# I2C_SWITCH.net
KiCad netlist of a schematic drawn in Altium Designer
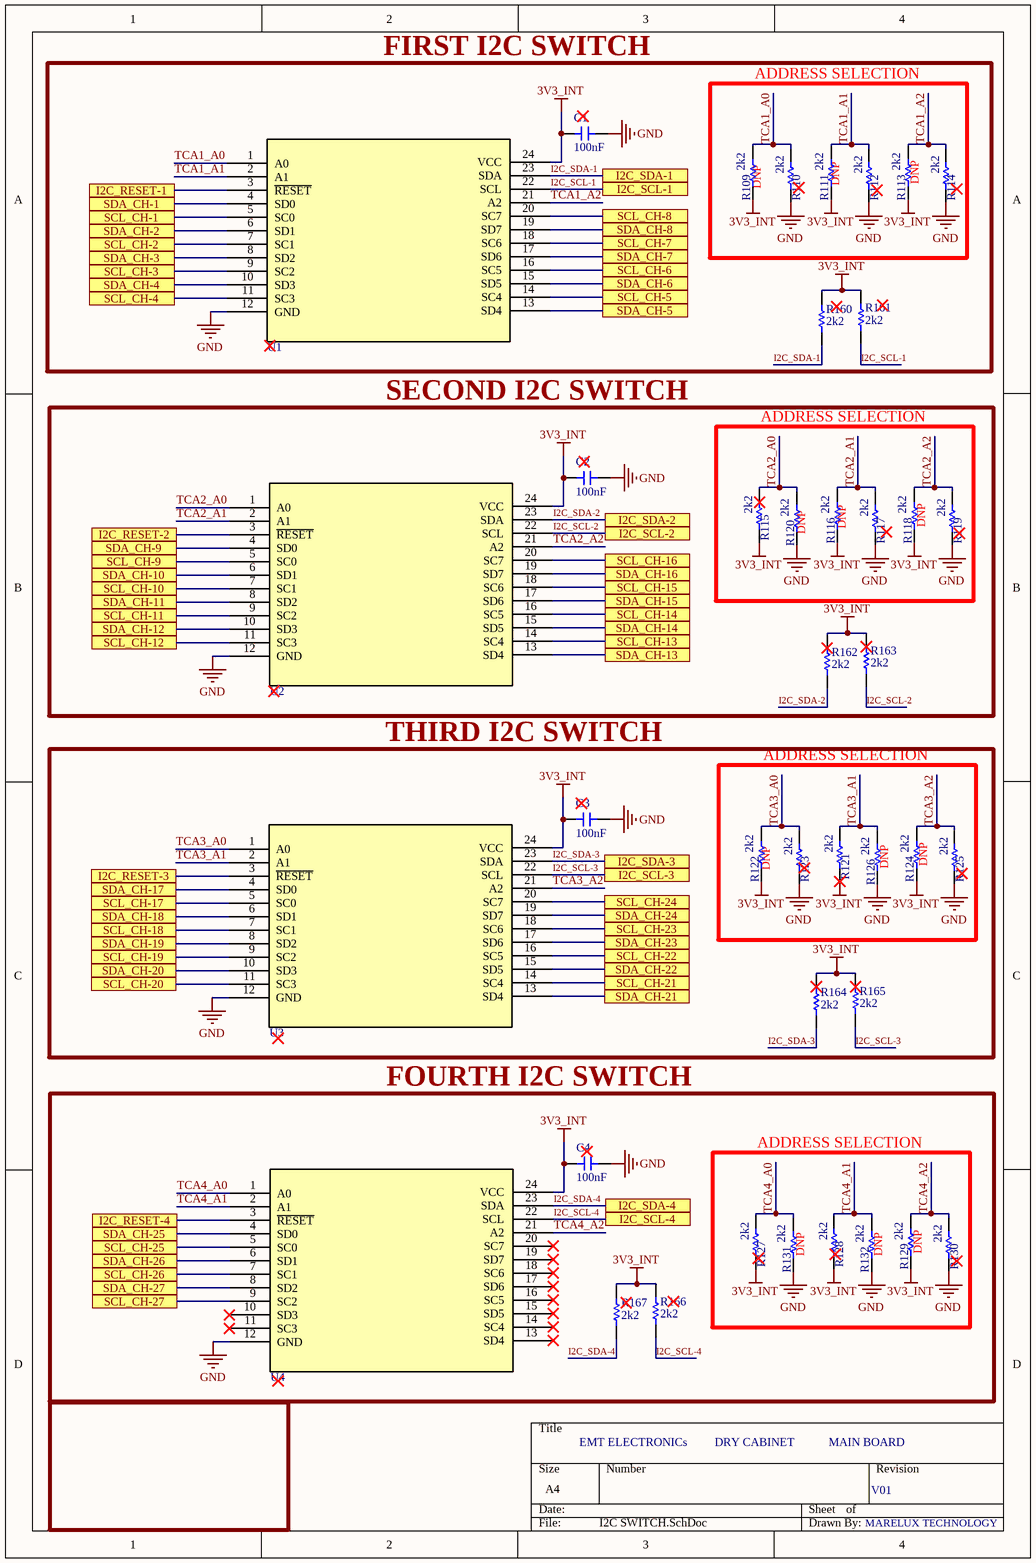
[diagram p0: I2C SWITCH.SchDoc]

(export (version "E")
  (design (tool "Eeschema 10.0.6"))
  (components
    (comp (ref "C1")
      (value "100nF")
      (footprint "MareLux24Lib:CAP_0402_CER")
      (description "100nF 0402 Ceramic Capacitor")
      (fields (field (name "PART NUMBER") "CL05B104KP5NNNC") (field (name "VOLTAGE") "10V"))
      (libsource (lib "MareLux24Lib") (part "CAP_GEN_CER"))
    )
    (comp (ref "C2")
      (value "100nF")
      (footprint "MareLux24Lib:CAP_0402_CER")
      (description "100nF 0402 Ceramic Capacitor")
      (fields (field (name "PART NUMBER") "CL05B104KP5NNNC") (field (name "VOLTAGE") "10V"))
      (libsource (lib "MareLux24Lib") (part "CAP_GEN_CER"))
    )
    (comp (ref "C3")
      (value "100nF")
      (footprint "MareLux24Lib:CAP_0402_CER")
      (description "100nF 0402 Ceramic Capacitor")
      (fields (field (name "PART NUMBER") "CL05B104KP5NNNC") (field (name "VOLTAGE") "10V"))
      (libsource (lib "MareLux24Lib") (part "CAP_GEN_CER"))
    )
    (comp (ref "C4")
      (value "100nF")
      (footprint "MareLux24Lib:CAP_0402_CER")
      (description "100nF 0402 Ceramic Capacitor")
      (fields (field (name "PART NUMBER") "CL05B104KP5NNNC") (field (name "VOLTAGE") "10V"))
      (libsource (lib "MareLux24Lib") (part "CAP_GEN_CER"))
    )
    (comp (ref "R109")
      (value "2k2")
      (footprint "MareLux24Lib:RES_0402_SMD")
      (description "Generic Chip Res 2k2")
      (fields
        (field (name "PART NUMBER") "RMCF0402JT2K20")
        (field (name "TOLERANCE") "5 %")
        (field (name "PLACE") "DNP")
      )
      (libsource (lib "MareLux24Lib") (part "RES_GEN_SMD"))
    )
    (comp (ref "R110")
      (value "2k2")
      (footprint "MareLux24Lib:RES_0402_SMD")
      (description "Generic Chip Res 2k2")
      (fields (field (name "PART NUMBER") "RMCF0402JT2K20") (field (name "TOLERANCE") "5 %"))
      (libsource (lib "MareLux24Lib") (part "RES_GEN_SMD"))
    )
    (comp (ref "R111")
      (value "2k2")
      (footprint "MareLux24Lib:RES_0402_SMD")
      (description "Generic Chip Res 2k2")
      (fields
        (field (name "PART NUMBER") "RMCF0402JT2K20")
        (field (name "TOLERANCE") "5 %")
        (field (name "PLACE") "DNP")
      )
      (libsource (lib "MareLux24Lib") (part "RES_GEN_SMD"))
    )
    (comp (ref "R112")
      (value "2k2")
      (footprint "MareLux24Lib:RES_0402_SMD")
      (description "Generic Chip Res 2k2")
      (fields (field (name "PART NUMBER") "RMCF0402JT2K20") (field (name "TOLERANCE") "5 %"))
      (libsource (lib "MareLux24Lib") (part "RES_GEN_SMD"))
    )
    (comp (ref "R113")
      (value "2k2")
      (footprint "MareLux24Lib:RES_0402_SMD")
      (description "Generic Chip Res 2k2")
      (fields
        (field (name "PART NUMBER") "RMCF0402JT2K20")
        (field (name "TOLERANCE") "5 %")
        (field (name "PLACE") "DNP")
      )
      (libsource (lib "MareLux24Lib") (part "RES_GEN_SMD"))
    )
    (comp (ref "R114")
      (value "2k2")
      (footprint "MareLux24Lib:RES_0402_SMD")
      (description "Generic Chip Res 2k2")
      (fields (field (name "PART NUMBER") "RMCF0402JT2K20") (field (name "TOLERANCE") "5 %"))
      (libsource (lib "MareLux24Lib") (part "RES_GEN_SMD"))
    )
    (comp (ref "R115")
      (value "2k2")
      (footprint "MareLux24Lib:RES_0402_SMD")
      (description "Generic Chip Res 2k2")
      (fields (field (name "PART NUMBER") "RMCF0402JT2K20") (field (name "TOLERANCE") "5 %"))
      (libsource (lib "MareLux24Lib") (part "RES_GEN_SMD"))
    )
    (comp (ref "R116")
      (value "2k2")
      (footprint "MareLux24Lib:RES_0402_SMD")
      (description "Generic Chip Res 2k2")
      (fields
        (field (name "PART NUMBER") "RMCF0402JT2K20")
        (field (name "TOLERANCE") "5 %")
        (field (name "PLACE") "DNP")
      )
      (libsource (lib "MareLux24Lib") (part "RES_GEN_SMD"))
    )
    (comp (ref "R117")
      (value "2k2")
      (footprint "MareLux24Lib:RES_0402_SMD")
      (description "Generic Chip Res 2k2")
      (fields (field (name "PART NUMBER") "RMCF0402JT2K20") (field (name "TOLERANCE") "5 %"))
      (libsource (lib "MareLux24Lib") (part "RES_GEN_SMD"))
    )
    (comp (ref "R118")
      (value "2k2")
      (footprint "MareLux24Lib:RES_0402_SMD")
      (description "Generic Chip Res 2k2")
      (fields
        (field (name "PART NUMBER") "RMCF0402JT2K20")
        (field (name "TOLERANCE") "5 %")
        (field (name "PLACE") "DNP")
      )
      (libsource (lib "MareLux24Lib") (part "RES_GEN_SMD"))
    )
    (comp (ref "R119")
      (value "2k2")
      (footprint "MareLux24Lib:RES_0402_SMD")
      (description "Generic Chip Res 2k2")
      (fields (field (name "PART NUMBER") "RMCF0402JT2K20") (field (name "TOLERANCE") "5 %"))
      (libsource (lib "MareLux24Lib") (part "RES_GEN_SMD"))
    )
    (comp (ref "R120")
      (value "2k2")
      (footprint "MareLux24Lib:RES_0402_SMD")
      (description "Generic Chip Res 2k2")
      (fields
        (field (name "PART NUMBER") "RMCF0402JT2K20")
        (field (name "TOLERANCE") "5 %")
        (field (name "PLACE") "DNP")
      )
      (libsource (lib "MareLux24Lib") (part "RES_GEN_SMD"))
    )
    (comp (ref "R121")
      (value "2k2")
      (footprint "MareLux24Lib:RES_0402_SMD")
      (description "Generic Chip Res 2k2")
      (fields (field (name "PART NUMBER") "RMCF0402JT2K20") (field (name "TOLERANCE") "5 %"))
      (libsource (lib "MareLux24Lib") (part "RES_GEN_SMD"))
    )
    (comp (ref "R122")
      (value "2k2")
      (footprint "MareLux24Lib:RES_0402_SMD")
      (description "Generic Chip Res 2k2")
      (fields
        (field (name "PART NUMBER") "RMCF0402JT2K20")
        (field (name "TOLERANCE") "5 %")
        (field (name "PLACE") "DNP")
      )
      (libsource (lib "MareLux24Lib") (part "RES_GEN_SMD"))
    )
    (comp (ref "R123")
      (value "2k2")
      (footprint "MareLux24Lib:RES_0402_SMD")
      (description "Generic Chip Res 2k2")
      (fields (field (name "PART NUMBER") "RMCF0402JT2K20") (field (name "TOLERANCE") "5 %"))
      (libsource (lib "MareLux24Lib") (part "RES_GEN_SMD"))
    )
    (comp (ref "R124")
      (value "2k2")
      (footprint "MareLux24Lib:RES_0402_SMD")
      (description "Generic Chip Res 2k2")
      (fields
        (field (name "PART NUMBER") "RMCF0402JT2K20")
        (field (name "TOLERANCE") "5 %")
        (field (name "PLACE") "DNP")
      )
      (libsource (lib "MareLux24Lib") (part "RES_GEN_SMD"))
    )
    (comp (ref "R125")
      (value "2k2")
      (footprint "MareLux24Lib:RES_0402_SMD")
      (description "Generic Chip Res 2k2")
      (fields (field (name "PART NUMBER") "RMCF0402JT2K20") (field (name "TOLERANCE") "5 %"))
      (libsource (lib "MareLux24Lib") (part "RES_GEN_SMD"))
    )
    (comp (ref "R126")
      (value "2k2")
      (footprint "MareLux24Lib:RES_0402_SMD")
      (description "Generic Chip Res 2k2")
      (fields
        (field (name "PART NUMBER") "RMCF0402JT2K20")
        (field (name "TOLERANCE") "5 %")
        (field (name "PLACE") "DNP")
      )
      (libsource (lib "MareLux24Lib") (part "RES_GEN_SMD"))
    )
    (comp (ref "R127")
      (value "2k2")
      (footprint "MareLux24Lib:RES_0402_SMD")
      (description "Generic Chip Res 2k2")
      (fields (field (name "PART NUMBER") "RMCF0402JT2K20") (field (name "TOLERANCE") "5 %"))
      (libsource (lib "MareLux24Lib") (part "RES_GEN_SMD"))
    )
    (comp (ref "R128")
      (value "2k2")
      (footprint "MareLux24Lib:RES_0402_SMD")
      (description "Generic Chip Res 2k2")
      (fields (field (name "PART NUMBER") "RMCF0402JT2K20") (field (name "TOLERANCE") "5 %"))
      (libsource (lib "MareLux24Lib") (part "RES_GEN_SMD"))
    )
    (comp (ref "R129")
      (value "2k2")
      (footprint "MareLux24Lib:RES_0402_SMD")
      (description "Generic Chip Res 2k2")
      (fields
        (field (name "PART NUMBER") "RMCF0402JT2K20")
        (field (name "TOLERANCE") "5 %")
        (field (name "PLACE") "DNP")
      )
      (libsource (lib "MareLux24Lib") (part "RES_GEN_SMD"))
    )
    (comp (ref "R130")
      (value "2k2")
      (footprint "MareLux24Lib:RES_0402_SMD")
      (description "Generic Chip Res 2k2")
      (fields (field (name "PART NUMBER") "RMCF0402JT2K20") (field (name "TOLERANCE") "5 %"))
      (libsource (lib "MareLux24Lib") (part "RES_GEN_SMD"))
    )
    (comp (ref "R131")
      (value "2k2")
      (footprint "MareLux24Lib:RES_0402_SMD")
      (description "Generic Chip Res 2k2")
      (fields
        (field (name "PART NUMBER") "RMCF0402JT2K20")
        (field (name "TOLERANCE") "5 %")
        (field (name "PLACE") "DNP")
      )
      (libsource (lib "MareLux24Lib") (part "RES_GEN_SMD"))
    )
    (comp (ref "R132")
      (value "2k2")
      (footprint "MareLux24Lib:RES_0402_SMD")
      (description "Generic Chip Res 2k2")
      (fields
        (field (name "PART NUMBER") "RMCF0402JT2K20")
        (field (name "TOLERANCE") "5 %")
        (field (name "PLACE") "DNP")
      )
      (libsource (lib "MareLux24Lib") (part "RES_GEN_SMD"))
    )
    (comp (ref "R160")
      (value "2k2")
      (footprint "MareLux24Lib:RES_0402_SMD")
      (description "Generic Chip Res 2k2")
      (fields (field (name "PART NUMBER") "RMCF0402JT2K20") (field (name "TOLERANCE") "5 %"))
      (libsource (lib "MareLux24Lib") (part "RES_GEN_SMD"))
    )
    (comp (ref "R161")
      (value "2k2")
      (footprint "MareLux24Lib:RES_0402_SMD")
      (description "Generic Chip Res 2k2")
      (fields (field (name "PART NUMBER") "RMCF0402JT2K20") (field (name "TOLERANCE") "5 %"))
      (libsource (lib "MareLux24Lib") (part "RES_GEN_SMD"))
    )
    (comp (ref "R162")
      (value "2k2")
      (footprint "MareLux24Lib:RES_0402_SMD")
      (description "Generic Chip Res 2k2")
      (fields (field (name "PART NUMBER") "RMCF0402JT2K20") (field (name "TOLERANCE") "5 %"))
      (libsource (lib "MareLux24Lib") (part "RES_GEN_SMD"))
    )
    (comp (ref "R163")
      (value "2k2")
      (footprint "MareLux24Lib:RES_0402_SMD")
      (description "Generic Chip Res 2k2")
      (fields (field (name "PART NUMBER") "RMCF0402JT2K20") (field (name "TOLERANCE") "5 %"))
      (libsource (lib "MareLux24Lib") (part "RES_GEN_SMD"))
    )
    (comp (ref "R164")
      (value "2k2")
      (footprint "MareLux24Lib:RES_0402_SMD")
      (description "Generic Chip Res 2k2")
      (fields (field (name "PART NUMBER") "RMCF0402JT2K20") (field (name "TOLERANCE") "5 %"))
      (libsource (lib "MareLux24Lib") (part "RES_GEN_SMD"))
    )
    (comp (ref "R165")
      (value "2k2")
      (footprint "MareLux24Lib:RES_0402_SMD")
      (description "Generic Chip Res 2k2")
      (fields (field (name "PART NUMBER") "RMCF0402JT2K20") (field (name "TOLERANCE") "5 %"))
      (libsource (lib "MareLux24Lib") (part "RES_GEN_SMD"))
    )
    (comp (ref "R166")
      (value "2k2")
      (footprint "MareLux24Lib:RES_0402_SMD")
      (description "Generic Chip Res 2k2")
      (fields (field (name "PART NUMBER") "RMCF0402JT2K20") (field (name "TOLERANCE") "5 %"))
      (libsource (lib "MareLux24Lib") (part "RES_GEN_SMD"))
    )
    (comp (ref "R167")
      (value "2k2")
      (footprint "MareLux24Lib:RES_0402_SMD")
      (description "Generic Chip Res 2k2")
      (fields (field (name "PART NUMBER") "RMCF0402JT2K20") (field (name "TOLERANCE") "5 %"))
      (libsource (lib "MareLux24Lib") (part "RES_GEN_SMD"))
    )
    (comp (ref "U1")
      (value "TCA9548APWR")
      (footprint "24-TSSOP")
      (description "IC BUS SWITCH 1 X 8:1 24TSSOP")
      (fields (field (name "MANUFACTURER") "Texas Instruments"))
      (libsource (lib "MareLux24Lib") (part "TCA9548APWR"))
    )
    (comp (ref "U2")
      (value "TCA9548APWR")
      (footprint "24-TSSOP")
      (description "IC BUS SWITCH 1 X 8:1 24TSSOP")
      (fields (field (name "MANUFACTURER") "Texas Instruments"))
      (libsource (lib "MareLux24Lib") (part "TCA9548APWR"))
    )
    (comp (ref "U3")
      (value "TCA9548APWR")
      (footprint "24-TSSOP")
      (description "IC BUS SWITCH 1 X 8:1 24TSSOP")
      (fields (field (name "MANUFACTURER") "Texas Instruments"))
      (libsource (lib "MareLux24Lib") (part "TCA9548APWR"))
    )
    (comp (ref "U4")
      (value "TCA9548APWR")
      (footprint "24-TSSOP")
      (description "IC BUS SWITCH 1 X 8:1 24TSSOP")
      (fields (field (name "MANUFACTURER") "Texas Instruments"))
      (libsource (lib "MareLux24Lib") (part "TCA9548APWR"))
    )
  )
  (nets
    (net (code "1") (name "/I2C_RESET-1") (class "Default")
      (node (ref "U1") (pin "3") (pinfunction "~{RESET}_3") (pintype "passive"))
    )
    (net (code "2") (name "/I2C_RESET-2") (class "Default")
      (node (ref "U2") (pin "3") (pinfunction "~{RESET}_3") (pintype "passive"))
    )
    (net (code "3") (name "/I2C_RESET-3") (class "Default")
      (node (ref "U3") (pin "3") (pinfunction "~{RESET}_3") (pintype "passive"))
    )
    (net (code "4") (name "/I2C_RESET-4") (class "Default")
      (node (ref "U4") (pin "3") (pinfunction "~{RESET}_3") (pintype "passive"))
    )
    (net (code "5") (name "/I2C_SCL-1") (class "Default")
      (node (ref "R161") (pin "1") (pinfunction "1_1") (pintype "passive"))
      (node (ref "U1") (pin "22") (pinfunction "SCL_22") (pintype "passive"))
    )
    (net (code "6") (name "/I2C_SCL-2") (class "Default")
      (node (ref "R163") (pin "1") (pinfunction "1_1") (pintype "passive"))
      (node (ref "U2") (pin "22") (pinfunction "SCL_22") (pintype "passive"))
    )
    (net (code "7") (name "/I2C_SCL-3") (class "Default")
      (node (ref "R165") (pin "1") (pinfunction "1_1") (pintype "passive"))
      (node (ref "U3") (pin "22") (pinfunction "SCL_22") (pintype "passive"))
    )
    (net (code "8") (name "/I2C_SCL-4") (class "Default")
      (node (ref "R166") (pin "1") (pinfunction "1_1") (pintype "passive"))
      (node (ref "U4") (pin "22") (pinfunction "SCL_22") (pintype "passive"))
    )
    (net (code "9") (name "/I2C_SDA-1") (class "Default")
      (node (ref "R160") (pin "1") (pinfunction "1_1") (pintype "passive"))
      (node (ref "U1") (pin "23") (pinfunction "SDA_23") (pintype "passive"))
    )
    (net (code "10") (name "/I2C_SDA-2") (class "Default")
      (node (ref "R162") (pin "1") (pinfunction "1_1") (pintype "passive"))
      (node (ref "U2") (pin "23") (pinfunction "SDA_23") (pintype "passive"))
    )
    (net (code "11") (name "/I2C_SDA-3") (class "Default")
      (node (ref "R164") (pin "1") (pinfunction "1_1") (pintype "passive"))
      (node (ref "U3") (pin "23") (pinfunction "SDA_23") (pintype "passive"))
    )
    (net (code "12") (name "/I2C_SDA-4") (class "Default")
      (node (ref "R167") (pin "1") (pinfunction "1_1") (pintype "passive"))
      (node (ref "U4") (pin "23") (pinfunction "SDA_23") (pintype "passive"))
    )
    (net (code "13") (name "/SCL_CH-1") (class "Default")
      (node (ref "U1") (pin "5") (pinfunction "SC0_5") (pintype "passive"))
    )
    (net (code "14") (name "/SCL_CH-2") (class "Default")
      (node (ref "U1") (pin "7") (pinfunction "SC1_7") (pintype "passive"))
    )
    (net (code "15") (name "/SCL_CH-3") (class "Default")
      (node (ref "U1") (pin "9") (pinfunction "SC2_9") (pintype "passive"))
    )
    (net (code "16") (name "/SCL_CH-4") (class "Default")
      (node (ref "U1") (pin "11") (pinfunction "SC3_11") (pintype "passive"))
    )
    (net (code "17") (name "/SCL_CH-5") (class "Default")
      (node (ref "U1") (pin "14") (pinfunction "SC4_14") (pintype "passive"))
    )
    (net (code "18") (name "/SCL_CH-6") (class "Default")
      (node (ref "U1") (pin "16") (pinfunction "SC5_16") (pintype "passive"))
    )
    (net (code "19") (name "/SCL_CH-7") (class "Default")
      (node (ref "U1") (pin "18") (pinfunction "SC6_18") (pintype "passive"))
    )
    (net (code "20") (name "/SCL_CH-8") (class "Default")
      (node (ref "U1") (pin "20") (pinfunction "SC7_20") (pintype "passive"))
    )
    (net (code "21") (name "/SCL_CH-9") (class "Default")
      (node (ref "U2") (pin "5") (pinfunction "SC0_5") (pintype "passive"))
    )
    (net (code "22") (name "/SCL_CH-10") (class "Default")
      (node (ref "U2") (pin "7") (pinfunction "SC1_7") (pintype "passive"))
    )
    (net (code "23") (name "/SCL_CH-11") (class "Default")
      (node (ref "U2") (pin "9") (pinfunction "SC2_9") (pintype "passive"))
    )
    (net (code "24") (name "/SCL_CH-12") (class "Default")
      (node (ref "U2") (pin "11") (pinfunction "SC3_11") (pintype "passive"))
    )
    (net (code "25") (name "/SCL_CH-13") (class "Default")
      (node (ref "U2") (pin "14") (pinfunction "SC4_14") (pintype "passive"))
    )
    (net (code "26") (name "/SCL_CH-14") (class "Default")
      (node (ref "U2") (pin "16") (pinfunction "SC5_16") (pintype "passive"))
    )
    (net (code "27") (name "/SCL_CH-15") (class "Default")
      (node (ref "U2") (pin "18") (pinfunction "SC6_18") (pintype "passive"))
    )
    (net (code "28") (name "/SCL_CH-16") (class "Default")
      (node (ref "U2") (pin "20") (pinfunction "SC7_20") (pintype "passive"))
    )
    (net (code "29") (name "/SCL_CH-17") (class "Default")
      (node (ref "U3") (pin "5") (pinfunction "SC0_5") (pintype "passive"))
    )
    (net (code "30") (name "/SCL_CH-18") (class "Default")
      (node (ref "U3") (pin "7") (pinfunction "SC1_7") (pintype "passive"))
    )
    (net (code "31") (name "/SCL_CH-19") (class "Default")
      (node (ref "U3") (pin "9") (pinfunction "SC2_9") (pintype "passive"))
    )
    (net (code "32") (name "/SCL_CH-20") (class "Default")
      (node (ref "U3") (pin "11") (pinfunction "SC3_11") (pintype "passive"))
    )
    (net (code "33") (name "/SCL_CH-21") (class "Default")
      (node (ref "U3") (pin "14") (pinfunction "SC4_14") (pintype "passive"))
    )
    (net (code "34") (name "/SCL_CH-22") (class "Default")
      (node (ref "U3") (pin "16") (pinfunction "SC5_16") (pintype "passive"))
    )
    (net (code "35") (name "/SCL_CH-23") (class "Default")
      (node (ref "U3") (pin "18") (pinfunction "SC6_18") (pintype "passive"))
    )
    (net (code "36") (name "/SCL_CH-24") (class "Default")
      (node (ref "U3") (pin "20") (pinfunction "SC7_20") (pintype "passive"))
    )
    (net (code "37") (name "/SCL_CH-25") (class "Default")
      (node (ref "U4") (pin "5") (pinfunction "SC0_5") (pintype "passive"))
    )
    (net (code "38") (name "/SCL_CH-26") (class "Default")
      (node (ref "U4") (pin "7") (pinfunction "SC1_7") (pintype "passive"))
    )
    (net (code "39") (name "/SCL_CH-27") (class "Default")
      (node (ref "U4") (pin "9") (pinfunction "SC2_9") (pintype "passive"))
    )
    (net (code "40") (name "/SDA_CH-1") (class "Default")
      (node (ref "U1") (pin "4") (pinfunction "SD0_4") (pintype "passive"))
    )
    (net (code "41") (name "/SDA_CH-2") (class "Default")
      (node (ref "U1") (pin "6") (pinfunction "SD1_6") (pintype "passive"))
    )
    (net (code "42") (name "/SDA_CH-3") (class "Default")
      (node (ref "U1") (pin "8") (pinfunction "SD2_8") (pintype "passive"))
    )
    (net (code "43") (name "/SDA_CH-4") (class "Default")
      (node (ref "U1") (pin "10") (pinfunction "SD3_10") (pintype "passive"))
    )
    (net (code "44") (name "/SDA_CH-5") (class "Default")
      (node (ref "U1") (pin "13") (pinfunction "SD4_13") (pintype "passive"))
    )
    (net (code "45") (name "/SDA_CH-6") (class "Default")
      (node (ref "U1") (pin "15") (pinfunction "SD5_15") (pintype "passive"))
    )
    (net (code "46") (name "/SDA_CH-7") (class "Default")
      (node (ref "U1") (pin "17") (pinfunction "SD6_17") (pintype "passive"))
    )
    (net (code "47") (name "/SDA_CH-8") (class "Default")
      (node (ref "U1") (pin "19") (pinfunction "SD7_19") (pintype "passive"))
    )
    (net (code "48") (name "/SDA_CH-9") (class "Default")
      (node (ref "U2") (pin "4") (pinfunction "SD0_4") (pintype "passive"))
    )
    (net (code "49") (name "/SDA_CH-10") (class "Default")
      (node (ref "U2") (pin "6") (pinfunction "SD1_6") (pintype "passive"))
    )
    (net (code "50") (name "/SDA_CH-11") (class "Default")
      (node (ref "U2") (pin "8") (pinfunction "SD2_8") (pintype "passive"))
    )
    (net (code "51") (name "/SDA_CH-12") (class "Default")
      (node (ref "U2") (pin "10") (pinfunction "SD3_10") (pintype "passive"))
    )
    (net (code "52") (name "/SDA_CH-13") (class "Default")
      (node (ref "U2") (pin "13") (pinfunction "SD4_13") (pintype "passive"))
    )
    (net (code "53") (name "/SDA_CH-14") (class "Default")
      (node (ref "U2") (pin "15") (pinfunction "SD5_15") (pintype "passive"))
    )
    (net (code "54") (name "/SDA_CH-15") (class "Default")
      (node (ref "U2") (pin "17") (pinfunction "SD6_17") (pintype "passive"))
    )
    (net (code "55") (name "/SDA_CH-16") (class "Default")
      (node (ref "U2") (pin "19") (pinfunction "SD7_19") (pintype "passive"))
    )
    (net (code "56") (name "/SDA_CH-17") (class "Default")
      (node (ref "U3") (pin "4") (pinfunction "SD0_4") (pintype "passive"))
    )
    (net (code "57") (name "/SDA_CH-18") (class "Default")
      (node (ref "U3") (pin "6") (pinfunction "SD1_6") (pintype "passive"))
    )
    (net (code "58") (name "/SDA_CH-19") (class "Default")
      (node (ref "U3") (pin "8") (pinfunction "SD2_8") (pintype "passive"))
    )
    (net (code "59") (name "/SDA_CH-20") (class "Default")
      (node (ref "U3") (pin "10") (pinfunction "SD3_10") (pintype "passive"))
    )
    (net (code "60") (name "/SDA_CH-21") (class "Default")
      (node (ref "U3") (pin "13") (pinfunction "SD4_13") (pintype "passive"))
    )
    (net (code "61") (name "/SDA_CH-22") (class "Default")
      (node (ref "U3") (pin "15") (pinfunction "SD5_15") (pintype "passive"))
    )
    (net (code "62") (name "/SDA_CH-23") (class "Default")
      (node (ref "U3") (pin "17") (pinfunction "SD6_17") (pintype "passive"))
    )
    (net (code "63") (name "/SDA_CH-24") (class "Default")
      (node (ref "U3") (pin "19") (pinfunction "SD7_19") (pintype "passive"))
    )
    (net (code "64") (name "/SDA_CH-25") (class "Default")
      (node (ref "U4") (pin "4") (pinfunction "SD0_4") (pintype "passive"))
    )
    (net (code "65") (name "/SDA_CH-26") (class "Default")
      (node (ref "U4") (pin "6") (pinfunction "SD1_6") (pintype "passive"))
    )
    (net (code "66") (name "/SDA_CH-27") (class "Default")
      (node (ref "U4") (pin "8") (pinfunction "SD2_8") (pintype "passive"))
    )
    (net (code "67") (name "/TCA1_A0") (class "Default")
      (node (ref "R109") (pin "1") (pinfunction "1_1") (pintype "passive"))
      (node (ref "R110") (pin "1") (pinfunction "1_1") (pintype "passive"))
      (node (ref "U1") (pin "1") (pinfunction "A0_1") (pintype "passive"))
    )
    (net (code "68") (name "/TCA1_A1") (class "Default")
      (node (ref "R111") (pin "1") (pinfunction "1_1") (pintype "passive"))
      (node (ref "R112") (pin "1") (pinfunction "1_1") (pintype "passive"))
      (node (ref "U1") (pin "2") (pinfunction "A1_2") (pintype "passive"))
    )
    (net (code "69") (name "/TCA1_A2") (class "Default")
      (node (ref "R113") (pin "1") (pinfunction "1_1") (pintype "passive"))
      (node (ref "R114") (pin "1") (pinfunction "1_1") (pintype "passive"))
      (node (ref "U1") (pin "21") (pinfunction "A2_21") (pintype "passive"))
    )
    (net (code "70") (name "/TCA2_A0") (class "Default")
      (node (ref "R115") (pin "1") (pinfunction "1_1") (pintype "passive"))
      (node (ref "R120") (pin "1") (pinfunction "1_1") (pintype "passive"))
      (node (ref "U2") (pin "1") (pinfunction "A0_1") (pintype "passive"))
    )
    (net (code "71") (name "/TCA2_A1") (class "Default")
      (node (ref "R116") (pin "1") (pinfunction "1_1") (pintype "passive"))
      (node (ref "R117") (pin "1") (pinfunction "1_1") (pintype "passive"))
      (node (ref "U2") (pin "2") (pinfunction "A1_2") (pintype "passive"))
    )
    (net (code "72") (name "/TCA2_A2") (class "Default")
      (node (ref "R118") (pin "1") (pinfunction "1_1") (pintype "passive"))
      (node (ref "R119") (pin "1") (pinfunction "1_1") (pintype "passive"))
      (node (ref "U2") (pin "21") (pinfunction "A2_21") (pintype "passive"))
    )
    (net (code "73") (name "/TCA3_A0") (class "Default")
      (node (ref "R122") (pin "1") (pinfunction "1_1") (pintype "passive"))
      (node (ref "R123") (pin "1") (pinfunction "1_1") (pintype "passive"))
      (node (ref "U3") (pin "1") (pinfunction "A0_1") (pintype "passive"))
    )
    (net (code "74") (name "/TCA3_A1") (class "Default")
      (node (ref "R121") (pin "1") (pinfunction "1_1") (pintype "passive"))
      (node (ref "R126") (pin "1") (pinfunction "1_1") (pintype "passive"))
      (node (ref "U3") (pin "2") (pinfunction "A1_2") (pintype "passive"))
    )
    (net (code "75") (name "/TCA3_A2") (class "Default")
      (node (ref "R124") (pin "1") (pinfunction "1_1") (pintype "passive"))
      (node (ref "R125") (pin "1") (pinfunction "1_1") (pintype "passive"))
      (node (ref "U3") (pin "21") (pinfunction "A2_21") (pintype "passive"))
    )
    (net (code "76") (name "/TCA4_A0") (class "Default")
      (node (ref "R127") (pin "1") (pinfunction "1_1") (pintype "passive"))
      (node (ref "R131") (pin "1") (pinfunction "1_1") (pintype "passive"))
      (node (ref "U4") (pin "1") (pinfunction "A0_1") (pintype "passive"))
    )
    (net (code "77") (name "/TCA4_A1") (class "Default")
      (node (ref "R128") (pin "1") (pinfunction "1_1") (pintype "passive"))
      (node (ref "R132") (pin "1") (pinfunction "1_1") (pintype "passive"))
      (node (ref "U4") (pin "2") (pinfunction "A1_2") (pintype "passive"))
    )
    (net (code "78") (name "/TCA4_A2") (class "Default")
      (node (ref "R129") (pin "1") (pinfunction "1_1") (pintype "passive"))
      (node (ref "R130") (pin "1") (pinfunction "1_1") (pintype "passive"))
      (node (ref "U4") (pin "21") (pinfunction "A2_21") (pintype "passive"))
    )
    (net (code "79") (name "3V3_INT") (class "Default")
      (node (ref "C1") (pin "2") (pinfunction "2_2") (pintype "passive"))
      (node (ref "C2") (pin "2") (pinfunction "2_2") (pintype "passive"))
      (node (ref "C3") (pin "2") (pinfunction "2_2") (pintype "passive"))
      (node (ref "C4") (pin "2") (pinfunction "2_2") (pintype "passive"))
      (node (ref "R109") (pin "2") (pinfunction "2_2") (pintype "passive"))
      (node (ref "R111") (pin "2") (pinfunction "2_2") (pintype "passive"))
      (node (ref "R113") (pin "2") (pinfunction "2_2") (pintype "passive"))
      (node (ref "R115") (pin "2") (pinfunction "2_2") (pintype "passive"))
      (node (ref "R116") (pin "2") (pinfunction "2_2") (pintype "passive"))
      (node (ref "R118") (pin "2") (pinfunction "2_2") (pintype "passive"))
      (node (ref "R121") (pin "2") (pinfunction "2_2") (pintype "passive"))
      (node (ref "R122") (pin "2") (pinfunction "2_2") (pintype "passive"))
      (node (ref "R124") (pin "2") (pinfunction "2_2") (pintype "passive"))
      (node (ref "R127") (pin "2") (pinfunction "2_2") (pintype "passive"))
      (node (ref "R128") (pin "2") (pinfunction "2_2") (pintype "passive"))
      (node (ref "R129") (pin "2") (pinfunction "2_2") (pintype "passive"))
      (node (ref "R160") (pin "2") (pinfunction "2_2") (pintype "passive"))
      (node (ref "R161") (pin "2") (pinfunction "2_2") (pintype "passive"))
      (node (ref "R162") (pin "2") (pinfunction "2_2") (pintype "passive"))
      (node (ref "R163") (pin "2") (pinfunction "2_2") (pintype "passive"))
      (node (ref "R164") (pin "2") (pinfunction "2_2") (pintype "passive"))
      (node (ref "R165") (pin "2") (pinfunction "2_2") (pintype "passive"))
      (node (ref "R166") (pin "2") (pinfunction "2_2") (pintype "passive"))
      (node (ref "R167") (pin "2") (pinfunction "2_2") (pintype "passive"))
      (node (ref "U1") (pin "24") (pinfunction "VCC_24") (pintype "passive"))
      (node (ref "U2") (pin "24") (pinfunction "VCC_24") (pintype "passive"))
      (node (ref "U3") (pin "24") (pinfunction "VCC_24") (pintype "passive"))
      (node (ref "U4") (pin "24") (pinfunction "VCC_24") (pintype "passive"))
    )
    (net (code "80") (name "GND") (class "Default")
      (node (ref "C1") (pin "1") (pinfunction "1_1") (pintype "passive"))
      (node (ref "C2") (pin "1") (pinfunction "1_1") (pintype "passive"))
      (node (ref "C3") (pin "1") (pinfunction "1_1") (pintype "passive"))
      (node (ref "C4") (pin "1") (pinfunction "1_1") (pintype "passive"))
      (node (ref "R110") (pin "2") (pinfunction "2_2") (pintype "passive"))
      (node (ref "R112") (pin "2") (pinfunction "2_2") (pintype "passive"))
      (node (ref "R114") (pin "2") (pinfunction "2_2") (pintype "passive"))
      (node (ref "R117") (pin "2") (pinfunction "2_2") (pintype "passive"))
      (node (ref "R119") (pin "2") (pinfunction "2_2") (pintype "passive"))
      (node (ref "R120") (pin "2") (pinfunction "2_2") (pintype "passive"))
      (node (ref "R123") (pin "2") (pinfunction "2_2") (pintype "passive"))
      (node (ref "R125") (pin "2") (pinfunction "2_2") (pintype "passive"))
      (node (ref "R126") (pin "2") (pinfunction "2_2") (pintype "passive"))
      (node (ref "R130") (pin "2") (pinfunction "2_2") (pintype "passive"))
      (node (ref "R131") (pin "2") (pinfunction "2_2") (pintype "passive"))
      (node (ref "R132") (pin "2") (pinfunction "2_2") (pintype "passive"))
      (node (ref "U1") (pin "12") (pinfunction "GND_12") (pintype "passive"))
      (node (ref "U2") (pin "12") (pinfunction "GND_12") (pintype "passive"))
      (node (ref "U3") (pin "12") (pinfunction "GND_12") (pintype "passive"))
      (node (ref "U4") (pin "12") (pinfunction "GND_12") (pintype "passive"))
    )
    (net (code "81") (name "unconnected-(U4-SC3-Pad11)") (class "Default")
      (node (ref "U4") (pin "11") (pinfunction "SC3_11") (pintype "passive+no_connect"))
    )
    (net (code "82") (name "unconnected-(U4-SC4-Pad14)") (class "Default")
      (node (ref "U4") (pin "14") (pinfunction "SC4_14") (pintype "passive+no_connect"))
    )
    (net (code "83") (name "unconnected-(U4-SC5-Pad16)") (class "Default")
      (node (ref "U4") (pin "16") (pinfunction "SC5_16") (pintype "passive+no_connect"))
    )
    (net (code "84") (name "unconnected-(U4-SC6-Pad18)") (class "Default")
      (node (ref "U4") (pin "18") (pinfunction "SC6_18") (pintype "passive+no_connect"))
    )
    (net (code "85") (name "unconnected-(U4-SC7-Pad20)") (class "Default")
      (node (ref "U4") (pin "20") (pinfunction "SC7_20") (pintype "passive+no_connect"))
    )
    (net (code "86") (name "unconnected-(U4-SD3-Pad10)") (class "Default")
      (node (ref "U4") (pin "10") (pinfunction "SD3_10") (pintype "passive+no_connect"))
    )
    (net (code "87") (name "unconnected-(U4-SD4-Pad13)") (class "Default")
      (node (ref "U4") (pin "13") (pinfunction "SD4_13") (pintype "passive+no_connect"))
    )
    (net (code "88") (name "unconnected-(U4-SD5-Pad15)") (class "Default")
      (node (ref "U4") (pin "15") (pinfunction "SD5_15") (pintype "passive+no_connect"))
    )
    (net (code "89") (name "unconnected-(U4-SD6-Pad17)") (class "Default")
      (node (ref "U4") (pin "17") (pinfunction "SD6_17") (pintype "passive+no_connect"))
    )
    (net (code "90") (name "unconnected-(U4-SD7-Pad19)") (class "Default")
      (node (ref "U4") (pin "19") (pinfunction "SD7_19") (pintype "passive+no_connect"))
    )
  )
)
